# TPS62730.net
KiCad netlist of a schematic drawn in EAGLE
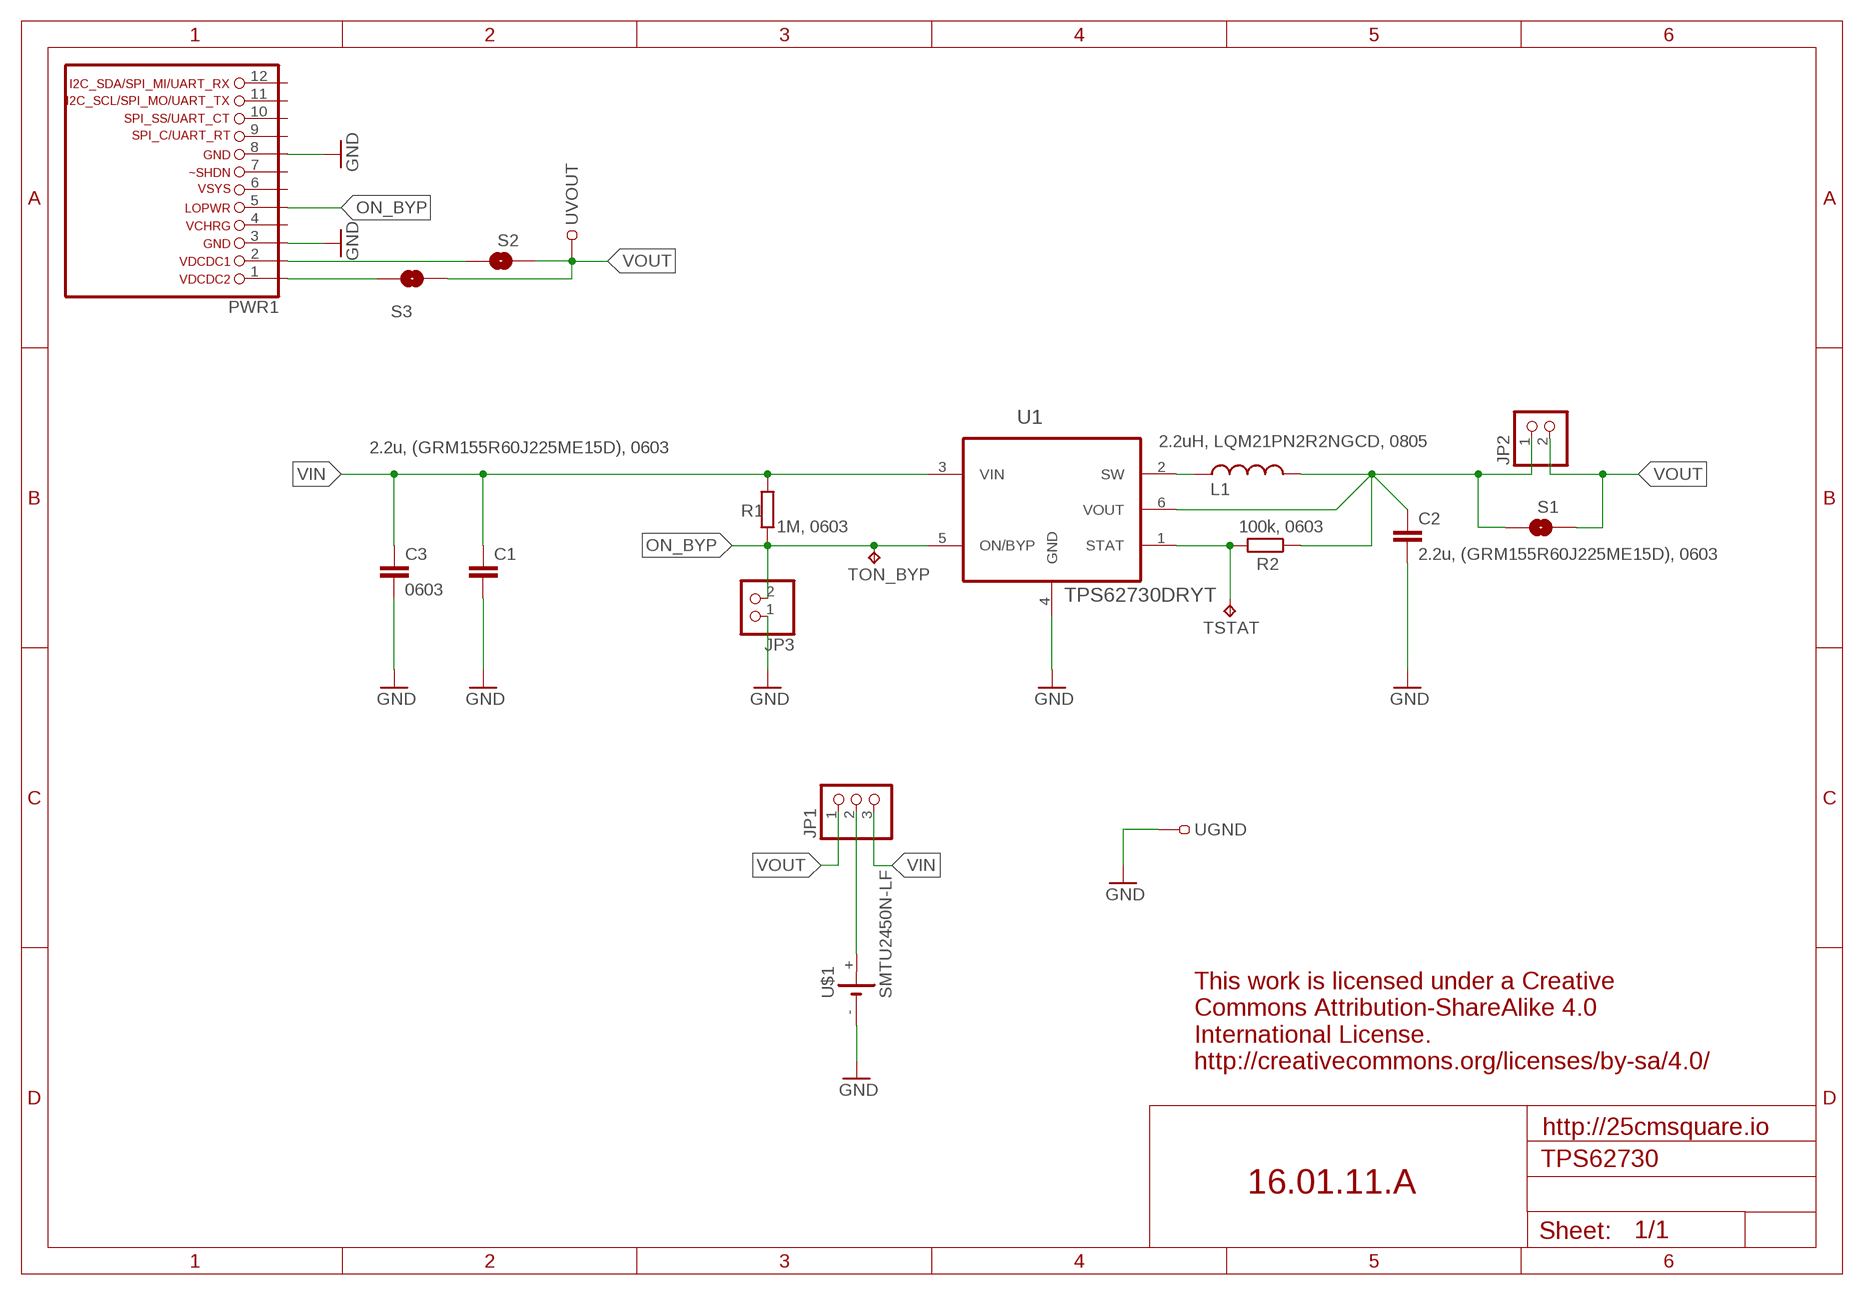
[diagram p0: schematic, sheet 1]

(export (version "E")
  (design (tool "Eeschema 10.0.6"))
  (components
    (comp (ref "C1")
      (value "2.2u, (GRM155R60J225ME15D), 0603")
      (footprint "eagle-import:C0603K")
      (libsource (lib "eagle-import") (part "C-EUC0603K"))
    )
    (comp (ref "C2")
      (value "2.2u, (GRM155R60J225ME15D), 0603")
      (footprint "eagle-import:C0603K")
      (libsource (lib "eagle-import") (part "C-EUC0603K"))
    )
    (comp (ref "C3")
      (value "0603")
      (footprint "eagle-import:C0603K")
      (libsource (lib "eagle-import") (part "C-EUC0603K"))
    )
    (comp (ref "JP1")
      (value "PINHD-1X3")
      (footprint "eagle-import:1X03")
      (libsource (lib "eagle-import") (part "PINHD-1X3"))
    )
    (comp (ref "JP2")
      (value "PINHD-1X2")
      (footprint "eagle-import:1X02")
      (libsource (lib "eagle-import") (part "PINHD-1X2"))
    )
    (comp (ref "JP3")
      (value "PINHD-1X2")
      (footprint "eagle-import:1X02")
      (libsource (lib "eagle-import") (part "PINHD-1X2"))
    )
    (comp (ref "L1")
      (value "2.2uH, LQM21PN2R2NGCD, 0805")
      (footprint "eagle-import:L0805")
      (libsource (lib "eagle-import") (part "L0805(2012)"))
    )
    (comp (ref "PWR1")
      (value "LIWE_12_PIN_PWR")
      (footprint "eagle-import:LIWE_12_PIN")
      (libsource (lib "eagle-import") (part "LIWE_12_PIN_PWR"))
    )
    (comp (ref "R1")
      (value "1M, 0603")
      (footprint "eagle-import:R0603")
      (libsource (lib "eagle-import") (part "R-EU_R0603"))
    )
    (comp (ref "R2")
      (value "100k, 0603")
      (footprint "eagle-import:R0603")
      (libsource (lib "eagle-import") (part "R-EU_R0603"))
    )
    (comp (ref "S1")
      (value "SOLDERJUMPERNC2")
      (footprint "eagle-import:SJ_2S-NOTRACE")
      (libsource (lib "eagle-import") (part "SOLDERJUMPERNC2"))
    )
    (comp (ref "S2")
      (value "SOLDERJUMPERNC2")
      (footprint "eagle-import:SJ_2S-NOTRACE")
      (libsource (lib "eagle-import") (part "SOLDERJUMPERNC2"))
    )
    (comp (ref "S3")
      (value "SOLDERJUMPERNC2")
      (footprint "eagle-import:SJ_2S-NOTRACE")
      (libsource (lib "eagle-import") (part "SOLDERJUMPERNC2"))
    )
    (comp (ref "TON_BYP")
      (value "TPTP14R")
      (footprint "eagle-import:TP14R")
      (libsource (lib "eagle-import") (part "TPTP14R"))
    )
    (comp (ref "TSTAT")
      (value "TPTP14R")
      (footprint "eagle-import:TP14R")
      (libsource (lib "eagle-import") (part "TPTP14R"))
    )
    (comp (ref "U$1")
      (value "SMTU2450N-LF")
      (footprint "eagle-import:SMTU2450N-LF")
      (libsource (lib "eagle-import") (part "SMTU2450N-LF"))
    )
    (comp (ref "U1")
      (value "TPS62730DRYT")
      (footprint "eagle-import:SON50P100X145X60-6N")
      (fields (field (name "MPN") "TPS62730DRYT "))
      (libsource (lib "eagle-import") (part "TPS62730DRYT"))
    )
    (comp (ref "UGND")
      (value "TEST-22-MULTICOMP")
      (footprint "eagle-import:TEST_1MM")
      (libsource (lib "eagle-import") (part "TEST-22-MULTICOMP"))
    )
    (comp (ref "UVOUT")
      (value "TEST-22-MULTICOMP")
      (footprint "eagle-import:TEST_1MM")
      (libsource (lib "eagle-import") (part "TEST-22-MULTICOMP"))
    )
  )
  (nets
    (net (code "1") (name "GND") (class "Default")
      (node (ref "C1") (pin "2") (pinfunction "2_2") (pintype "passive"))
      (node (ref "C2") (pin "2") (pinfunction "2_2") (pintype "passive"))
      (node (ref "C3") (pin "2") (pinfunction "2_2") (pintype "passive"))
      (node (ref "JP3") (pin "1") (pinfunction "1_1") (pintype "passive"))
      (node (ref "PWR1") (pin "3") (pinfunction "3_3") (pintype "passive"))
      (node (ref "PWR1") (pin "8") (pinfunction "8_8") (pintype "passive"))
      (node (ref "U$1") (pin "-") (pinfunction "-_-") (pintype "passive"))
      (node (ref "U1") (pin "4") (pinfunction "GND_4") (pintype "passive"))
      (node (ref "UGND") (pin "1") (pinfunction "1_1") (pintype "passive"))
    )
    (net (code "2") (name "Net-(JP1-Pad2)") (class "Default")
      (node (ref "JP1") (pin "2") (pinfunction "2_2") (pintype "passive"))
      (node (ref "U$1") (pin "+") (pinfunction "+_+") (pintype "passive"))
    )
    (net (code "3") (name "Net-(PWR1-Pad1)") (class "Default")
      (node (ref "PWR1") (pin "1") (pinfunction "1_1") (pintype "passive"))
      (node (ref "S3") (pin "1") (pinfunction "1_1") (pintype "passive"))
    )
    (net (code "4") (name "Net-(PWR1-Pad2)") (class "Default")
      (node (ref "PWR1") (pin "2") (pinfunction "2_2") (pintype "passive"))
      (node (ref "S2") (pin "1") (pinfunction "1_1") (pintype "passive"))
    )
    (net (code "5") (name "Net-(U1-STAT)") (class "Default")
      (node (ref "R2") (pin "2") (pinfunction "2_2") (pintype "passive"))
      (node (ref "TSTAT") (pin "TP") (pinfunction "TP_TP") (pintype "input"))
      (node (ref "U1") (pin "1") (pinfunction "STAT_1") (pintype "output"))
    )
    (net (code "6") (name "Net-(U1-SW)") (class "Default")
      (node (ref "L1") (pin "1") (pinfunction "1_1") (pintype "passive"))
      (node (ref "U1") (pin "2") (pinfunction "SW_2") (pintype "output"))
    )
    (net (code "7") (name "Net-(U1-VOUT)") (class "Default")
      (node (ref "C2") (pin "1") (pinfunction "1_1") (pintype "passive"))
      (node (ref "JP2") (pin "1") (pinfunction "1_1") (pintype "passive"))
      (node (ref "L1") (pin "2") (pinfunction "2_2") (pintype "passive"))
      (node (ref "R2") (pin "1") (pinfunction "1_1") (pintype "passive"))
      (node (ref "S1") (pin "1") (pinfunction "1_1") (pintype "passive"))
      (node (ref "U1") (pin "6") (pinfunction "VOUT_6") (pintype "passive"))
    )
    (net (code "8") (name "ON_BYP") (class "Default")
      (node (ref "JP3") (pin "2") (pinfunction "2_2") (pintype "passive"))
      (node (ref "PWR1") (pin "5") (pinfunction "5_5") (pintype "passive"))
      (node (ref "R1") (pin "1") (pinfunction "1_1") (pintype "passive"))
      (node (ref "TON_BYP") (pin "TP") (pinfunction "TP_TP") (pintype "input"))
      (node (ref "U1") (pin "5") (pinfunction "ON/BYP_5") (pintype "input"))
    )
    (net (code "9") (name "VIN") (class "Default")
      (node (ref "C1") (pin "1") (pinfunction "1_1") (pintype "passive"))
      (node (ref "C3") (pin "1") (pinfunction "1_1") (pintype "passive"))
      (node (ref "JP1") (pin "3") (pinfunction "3_3") (pintype "passive"))
      (node (ref "R1") (pin "2") (pinfunction "2_2") (pintype "passive"))
      (node (ref "U1") (pin "3") (pinfunction "VIN_3") (pintype "power_in"))
    )
    (net (code "10") (name "VOUT") (class "Default")
      (node (ref "JP1") (pin "1") (pinfunction "1_1") (pintype "passive"))
      (node (ref "JP2") (pin "2") (pinfunction "2_2") (pintype "passive"))
      (node (ref "S1") (pin "2") (pinfunction "2_2") (pintype "passive"))
      (node (ref "S2") (pin "2") (pinfunction "2_2") (pintype "passive"))
      (node (ref "S3") (pin "2") (pinfunction "2_2") (pintype "passive"))
      (node (ref "UVOUT") (pin "1") (pinfunction "1_1") (pintype "passive"))
    )
    (net (code "11") (name "unconnected-(PWR1-Pad4)") (class "Default")
      (node (ref "PWR1") (pin "4") (pinfunction "4_4") (pintype "passive"))
    )
    (net (code "12") (name "unconnected-(PWR1-Pad6)") (class "Default")
      (node (ref "PWR1") (pin "6") (pinfunction "6_6") (pintype "passive"))
    )
    (net (code "13") (name "unconnected-(PWR1-Pad7)") (class "Default")
      (node (ref "PWR1") (pin "7") (pinfunction "7_7") (pintype "passive"))
    )
    (net (code "14") (name "unconnected-(PWR1-Pad9)") (class "Default")
      (node (ref "PWR1") (pin "9") (pinfunction "9_9") (pintype "passive"))
    )
    (net (code "15") (name "unconnected-(PWR1-Pad10)") (class "Default")
      (node (ref "PWR1") (pin "10") (pinfunction "10_10") (pintype "passive"))
    )
    (net (code "16") (name "unconnected-(PWR1-Pad11)") (class "Default")
      (node (ref "PWR1") (pin "11") (pinfunction "11_11") (pintype "passive"))
    )
    (net (code "17") (name "unconnected-(PWR1-Pad12)") (class "Default")
      (node (ref "PWR1") (pin "12") (pinfunction "12_12") (pintype "passive"))
    )
  )
)
